# Lighting_Board.net
KiCad netlist of a schematic drawn in EAGLE
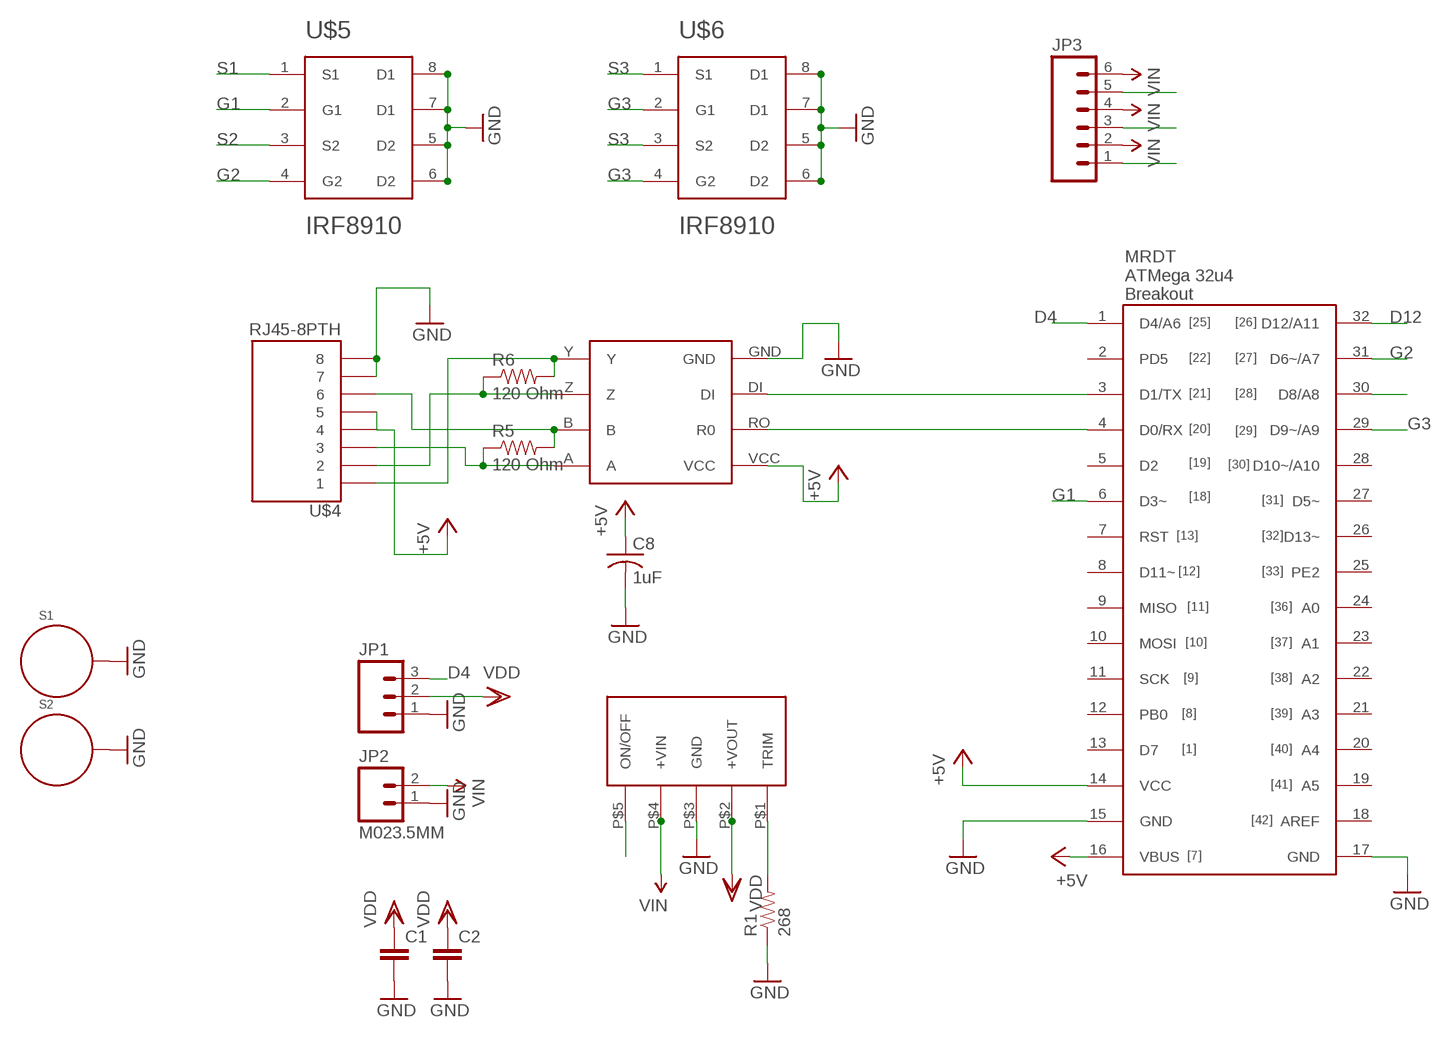
[diagram p0: schematic, sheet 1]

(export (version "E")
  (design (tool "Eeschema 10.0.6"))
  (components
    (comp (ref "C1")
      (value "CAP1206")
      (footprint "eagle-import:1206")
      (libsource (lib "eagle-import") (part "CAP1206"))
    )
    (comp (ref "C2")
      (value "CAP1206")
      (footprint "eagle-import:1206")
      (libsource (lib "eagle-import") (part "CAP1206"))
    )
    (comp (ref "C8")
      (value "1uF")
      (footprint "eagle-import:C1206")
      (libsource (lib "eagle-import") (part "C-USC1206"))
    )
    (comp (ref "JP1")
      (value "M03SCREW")
      (footprint "eagle-import:SCREWTERMINAL-3.5MM-3")
      (libsource (lib "eagle-import") (part "M03SCREW"))
    )
    (comp (ref "JP2")
      (value "M023.5MM")
      (footprint "eagle-import:SCREWTERMINAL-3.5MM-2")
      (libsource (lib "eagle-import") (part "M023.5MM"))
    )
    (comp (ref "JP3")
      (value "M063.5MM-6")
      (footprint "eagle-import:SCREWTERMINAL-3.5MM-6")
      (libsource (lib "eagle-import") (part "M063.5MM-6"))
    )
    (comp (ref "R1")
      (value "268")
      (footprint "eagle-import:1206")
      (libsource (lib "eagle-import") (part "RESISTOR1206"))
    )
    (comp (ref "R5")
      (value "120 Ohm")
      (footprint "eagle-import:1206")
      (libsource (lib "eagle-import") (part "RESISTOR1206"))
    )
    (comp (ref "R6")
      (value "120 Ohm")
      (footprint "eagle-import:1206")
      (libsource (lib "eagle-import") (part "RESISTOR1206"))
    )
    (comp (ref "S1")
      (value "STANDOFF_ELECTRICAL")
      (footprint "eagle-import:STANDOFF-ELECTRICAL")
      (libsource (lib "eagle-import") (part "STANDOFF_ELECTRICAL"))
    )
    (comp (ref "S2")
      (value "STANDOFF_ELECTRICAL")
      (footprint "eagle-import:STANDOFF-ELECTRICAL")
      (libsource (lib "eagle-import") (part "STANDOFF_ELECTRICAL"))
    )
    (comp (ref "U$1")
      (value "OKR-T/10-W12-C")
      (footprint "eagle-import:OKR-T_10-W12-C")
      (libsource (lib "eagle-import") (part "OKR-T/10-W12-C"))
    )
    (comp (ref "U$2")
      (value "32U4_BREAKOUT")
      (footprint "eagle-import:32U4_MCU_DIP")
      (libsource (lib "eagle-import") (part "32U4_BREAKOUT"))
    )
    (comp (ref "U$3")
      (value "MAX3077")
      (footprint "eagle-import:MAX3070E")
      (libsource (lib "eagle-import") (part "MAX3077"))
    )
    (comp (ref "U$4")
      (value "RJ45-8PTH")
      (footprint "eagle-import:RJ45-8")
      (libsource (lib "eagle-import") (part "RJ45-8PTH"))
    )
    (comp (ref "U$5")
      (value "IRF8910")
      (footprint "eagle-import:SO8")
      (libsource (lib "eagle-import") (part "IRF8910"))
    )
    (comp (ref "U$6")
      (value "IRF8910")
      (footprint "eagle-import:SO8")
      (libsource (lib "eagle-import") (part "IRF8910"))
    )
  )
  (nets
    (net (code "1") (name "+5V") (class "Default")
      (node (ref "C8") (pin "1") (pinfunction "1_1") (pintype "passive"))
      (node (ref "U$2") (pin "14") (pinfunction "VCC_14") (pintype "bidirectional"))
      (node (ref "U$2") (pin "16") (pinfunction "VBUS_16") (pintype "bidirectional"))
      (node (ref "U$3") (pin "VCC") (pinfunction "VCC_VCC") (pintype "bidirectional"))
      (node (ref "U$4") (pin "4") (pinfunction "4_4") (pintype "bidirectional"))
      (node (ref "U$4") (pin "5") (pinfunction "5_5") (pintype "bidirectional"))
    )
    (net (code "2") (name "/D4") (class "Default")
      (node (ref "JP1") (pin "3") (pinfunction "3_3") (pintype "passive"))
      (node (ref "U$2") (pin "1") (pinfunction "D4/A6_1") (pintype "bidirectional"))
    )
    (net (code "3") (name "/D8") (class "Default")
      (node (ref "U$1") (pin "P$5") (pinfunction "ON/OFF_P$5") (pintype "bidirectional"))
      (node (ref "U$2") (pin "30") (pinfunction "D8/A8_30") (pintype "bidirectional"))
    )
    (net (code "4") (name "/D12") (class "Default")
      (node (ref "U$2") (pin "32") (pinfunction "D12/A11_32") (pintype "bidirectional"))
    )
    (net (code "5") (name "/G1") (class "Default")
      (node (ref "U$2") (pin "6") (pinfunction "D3~{}_6") (pintype "bidirectional"))
      (node (ref "U$5") (pin "2") (pinfunction "G1_2") (pintype "bidirectional"))
    )
    (net (code "6") (name "/G2") (class "Default")
      (node (ref "U$2") (pin "31") (pinfunction "D6~{/A7}_31") (pintype "bidirectional"))
      (node (ref "U$5") (pin "4") (pinfunction "G2_4") (pintype "bidirectional"))
    )
    (net (code "7") (name "/G3") (class "Default")
      (node (ref "U$2") (pin "29") (pinfunction "D9~{/A9}_29") (pintype "bidirectional"))
      (node (ref "U$6") (pin "2") (pinfunction "G1_2") (pintype "bidirectional"))
      (node (ref "U$6") (pin "4") (pinfunction "G2_4") (pintype "bidirectional"))
    )
    (net (code "8") (name "/S1") (class "Default")
      (node (ref "JP3") (pin "5") (pinfunction "5_5") (pintype "passive"))
      (node (ref "U$5") (pin "1") (pinfunction "S1_1") (pintype "bidirectional"))
    )
    (net (code "9") (name "/S2") (class "Default")
      (node (ref "JP3") (pin "3") (pinfunction "3_3") (pintype "passive"))
      (node (ref "U$5") (pin "3") (pinfunction "S2_3") (pintype "bidirectional"))
    )
    (net (code "10") (name "/S3") (class "Default")
      (node (ref "JP3") (pin "1") (pinfunction "1_1") (pintype "passive"))
      (node (ref "U$6") (pin "1") (pinfunction "S1_1") (pintype "bidirectional"))
      (node (ref "U$6") (pin "3") (pinfunction "S2_3") (pintype "bidirectional"))
    )
    (net (code "11") (name "GND") (class "Default")
      (node (ref "C1") (pin "2") (pinfunction "2_2") (pintype "passive"))
      (node (ref "C2") (pin "2") (pinfunction "2_2") (pintype "passive"))
      (node (ref "C8") (pin "2") (pinfunction "2_2") (pintype "passive"))
      (node (ref "JP1") (pin "1") (pinfunction "1_1") (pintype "passive"))
      (node (ref "JP2") (pin "1") (pinfunction "1_1") (pintype "passive"))
      (node (ref "R1") (pin "1") (pinfunction "1_1") (pintype "passive"))
      (node (ref "S1") (pin "P1") (pinfunction "P$1_P1") (pintype "bidirectional"))
      (node (ref "S2") (pin "P1") (pinfunction "P$1_P1") (pintype "bidirectional"))
      (node (ref "U$1") (pin "P$3") (pinfunction "GND_P$3") (pintype "bidirectional"))
      (node (ref "U$2") (pin "15") (pinfunction "GND_15") (pintype "bidirectional"))
      (node (ref "U$2") (pin "17") (pinfunction "GND_17") (pintype "bidirectional"))
      (node (ref "U$3") (pin "GND") (pinfunction "GND_GND") (pintype "bidirectional"))
      (node (ref "U$4") (pin "7") (pinfunction "7_7") (pintype "bidirectional"))
      (node (ref "U$4") (pin "8") (pinfunction "8_8") (pintype "bidirectional"))
      (node (ref "U$5") (pin "5") (pinfunction "D2_5") (pintype "bidirectional"))
      (node (ref "U$5") (pin "6") (pinfunction "D2_6") (pintype "bidirectional"))
      (node (ref "U$5") (pin "7") (pinfunction "D1_7") (pintype "bidirectional"))
      (node (ref "U$5") (pin "8") (pinfunction "D1_8") (pintype "bidirectional"))
      (node (ref "U$6") (pin "5") (pinfunction "D2_5") (pintype "bidirectional"))
      (node (ref "U$6") (pin "6") (pinfunction "D2_6") (pintype "bidirectional"))
      (node (ref "U$6") (pin "7") (pinfunction "D1_7") (pintype "bidirectional"))
      (node (ref "U$6") (pin "8") (pinfunction "D1_8") (pintype "bidirectional"))
    )
    (net (code "12") (name "Net-(R5-Pad1)") (class "Default")
      (node (ref "R5") (pin "1") (pinfunction "1_1") (pintype "passive"))
      (node (ref "U$3") (pin "A") (pinfunction "A_A") (pintype "bidirectional"))
      (node (ref "U$4") (pin "3") (pinfunction "3_3") (pintype "bidirectional"))
    )
    (net (code "13") (name "Net-(R5-Pad2)") (class "Default")
      (node (ref "R5") (pin "2") (pinfunction "2_2") (pintype "passive"))
      (node (ref "U$3") (pin "B") (pinfunction "B_B") (pintype "bidirectional"))
      (node (ref "U$4") (pin "6") (pinfunction "6_6") (pintype "bidirectional"))
    )
    (net (code "14") (name "Net-(R6-Pad1)") (class "Default")
      (node (ref "R6") (pin "1") (pinfunction "1_1") (pintype "passive"))
      (node (ref "U$3") (pin "Z") (pinfunction "Z_Z") (pintype "bidirectional"))
      (node (ref "U$4") (pin "2") (pinfunction "2_2") (pintype "bidirectional"))
    )
    (net (code "15") (name "Net-(R6-Pad2)") (class "Default")
      (node (ref "R6") (pin "2") (pinfunction "2_2") (pintype "passive"))
      (node (ref "U$3") (pin "Y") (pinfunction "Y_Y") (pintype "bidirectional"))
      (node (ref "U$4") (pin "1") (pinfunction "1_1") (pintype "bidirectional"))
    )
    (net (code "16") (name "Net-(U$1-TRIM)") (class "Default")
      (node (ref "R1") (pin "2") (pinfunction "2_2") (pintype "passive"))
      (node (ref "U$1") (pin "P$1") (pinfunction "TRIM_P$1") (pintype "bidirectional"))
    )
    (net (code "17") (name "Net-(U$2-D0{slash}RX)") (class "Default")
      (node (ref "U$2") (pin "4") (pinfunction "D0/RX_4") (pintype "bidirectional"))
      (node (ref "U$3") (pin "RO") (pinfunction "R0_RO") (pintype "bidirectional"))
    )
    (net (code "18") (name "Net-(U$2-D1{slash}TX)") (class "Default")
      (node (ref "U$2") (pin "3") (pinfunction "D1/TX_3") (pintype "bidirectional"))
      (node (ref "U$3") (pin "DI") (pinfunction "DI_DI") (pintype "bidirectional"))
    )
    (net (code "19") (name "VDD") (class "Default")
      (node (ref "C1") (pin "1") (pinfunction "1_1") (pintype "passive"))
      (node (ref "C2") (pin "1") (pinfunction "1_1") (pintype "passive"))
      (node (ref "JP1") (pin "2") (pinfunction "2_2") (pintype "passive"))
      (node (ref "U$1") (pin "P$2") (pinfunction "+VOUT_P$2") (pintype "bidirectional"))
    )
    (net (code "20") (name "VIN") (class "Default")
      (node (ref "JP2") (pin "2") (pinfunction "2_2") (pintype "passive"))
      (node (ref "JP3") (pin "2") (pinfunction "2_2") (pintype "passive"))
      (node (ref "JP3") (pin "4") (pinfunction "4_4") (pintype "passive"))
      (node (ref "JP3") (pin "6") (pinfunction "6_6") (pintype "passive"))
      (node (ref "U$1") (pin "P$4") (pinfunction "+VIN_P$4") (pintype "bidirectional"))
    )
    (net (code "21") (name "unconnected-(U$2-A0-Pad24)") (class "Default")
      (node (ref "U$2") (pin "24") (pinfunction "A0_24") (pintype "bidirectional"))
    )
    (net (code "22") (name "unconnected-(U$2-A1-Pad23)") (class "Default")
      (node (ref "U$2") (pin "23") (pinfunction "A1_23") (pintype "bidirectional"))
    )
    (net (code "23") (name "unconnected-(U$2-A2-Pad22)") (class "Default")
      (node (ref "U$2") (pin "22") (pinfunction "A2_22") (pintype "bidirectional"))
    )
    (net (code "24") (name "unconnected-(U$2-A3-Pad21)") (class "Default")
      (node (ref "U$2") (pin "21") (pinfunction "A3_21") (pintype "bidirectional"))
    )
    (net (code "25") (name "unconnected-(U$2-A4-Pad20)") (class "Default")
      (node (ref "U$2") (pin "20") (pinfunction "A4_20") (pintype "bidirectional"))
    )
    (net (code "26") (name "unconnected-(U$2-A5-Pad19)") (class "Default")
      (node (ref "U$2") (pin "19") (pinfunction "A5_19") (pintype "bidirectional"))
    )
    (net (code "27") (name "unconnected-(U$2-AREF-Pad18)") (class "Default")
      (node (ref "U$2") (pin "18") (pinfunction "AREF_18") (pintype "bidirectional"))
    )
    (net (code "28") (name "unconnected-(U$2-D2-Pad5)") (class "Default")
      (node (ref "U$2") (pin "5") (pinfunction "D2_5") (pintype "bidirectional"))
    )
    (net (code "29") (name "unconnected-(U$2-D5~{}-Pad27)") (class "Default")
      (node (ref "U$2") (pin "27") (pinfunction "D5~{}_27") (pintype "bidirectional"))
    )
    (net (code "30") (name "unconnected-(U$2-D7-Pad13)") (class "Default")
      (node (ref "U$2") (pin "13") (pinfunction "D7_13") (pintype "bidirectional"))
    )
    (net (code "31") (name "unconnected-(U$2-D10~{{slash}A10}-Pad28)") (class "Default")
      (node (ref "U$2") (pin "28") (pinfunction "D10~{/A10}_28") (pintype "bidirectional"))
    )
    (net (code "32") (name "unconnected-(U$2-D11~{}-Pad8)") (class "Default")
      (node (ref "U$2") (pin "8") (pinfunction "D11~{}_8") (pintype "bidirectional"))
    )
    (net (code "33") (name "unconnected-(U$2-D13~{}-Pad26)") (class "Default")
      (node (ref "U$2") (pin "26") (pinfunction "D13~{}_26") (pintype "bidirectional"))
    )
    (net (code "34") (name "unconnected-(U$2-MISO-Pad9)") (class "Default")
      (node (ref "U$2") (pin "9") (pinfunction "MISO_9") (pintype "bidirectional"))
    )
    (net (code "35") (name "unconnected-(U$2-MOSI-Pad10)") (class "Default")
      (node (ref "U$2") (pin "10") (pinfunction "MOSI_10") (pintype "bidirectional"))
    )
    (net (code "36") (name "unconnected-(U$2-PB0-Pad12)") (class "Default")
      (node (ref "U$2") (pin "12") (pinfunction "PB0_12") (pintype "bidirectional"))
    )
    (net (code "37") (name "unconnected-(U$2-PD5-Pad2)") (class "Default")
      (node (ref "U$2") (pin "2") (pinfunction "PD5_2") (pintype "bidirectional"))
    )
    (net (code "38") (name "unconnected-(U$2-PE2-Pad25)") (class "Default")
      (node (ref "U$2") (pin "25") (pinfunction "PE2_25") (pintype "bidirectional"))
    )
    (net (code "39") (name "unconnected-(U$2-RST-Pad7)") (class "Default")
      (node (ref "U$2") (pin "7") (pinfunction "RST_7") (pintype "bidirectional"))
    )
    (net (code "40") (name "unconnected-(U$2-SCK-Pad11)") (class "Default")
      (node (ref "U$2") (pin "11") (pinfunction "SCK_11") (pintype "bidirectional"))
    )
  )
)
